# main.net
KiCad netlist of a schematic drawn in Altium Designer
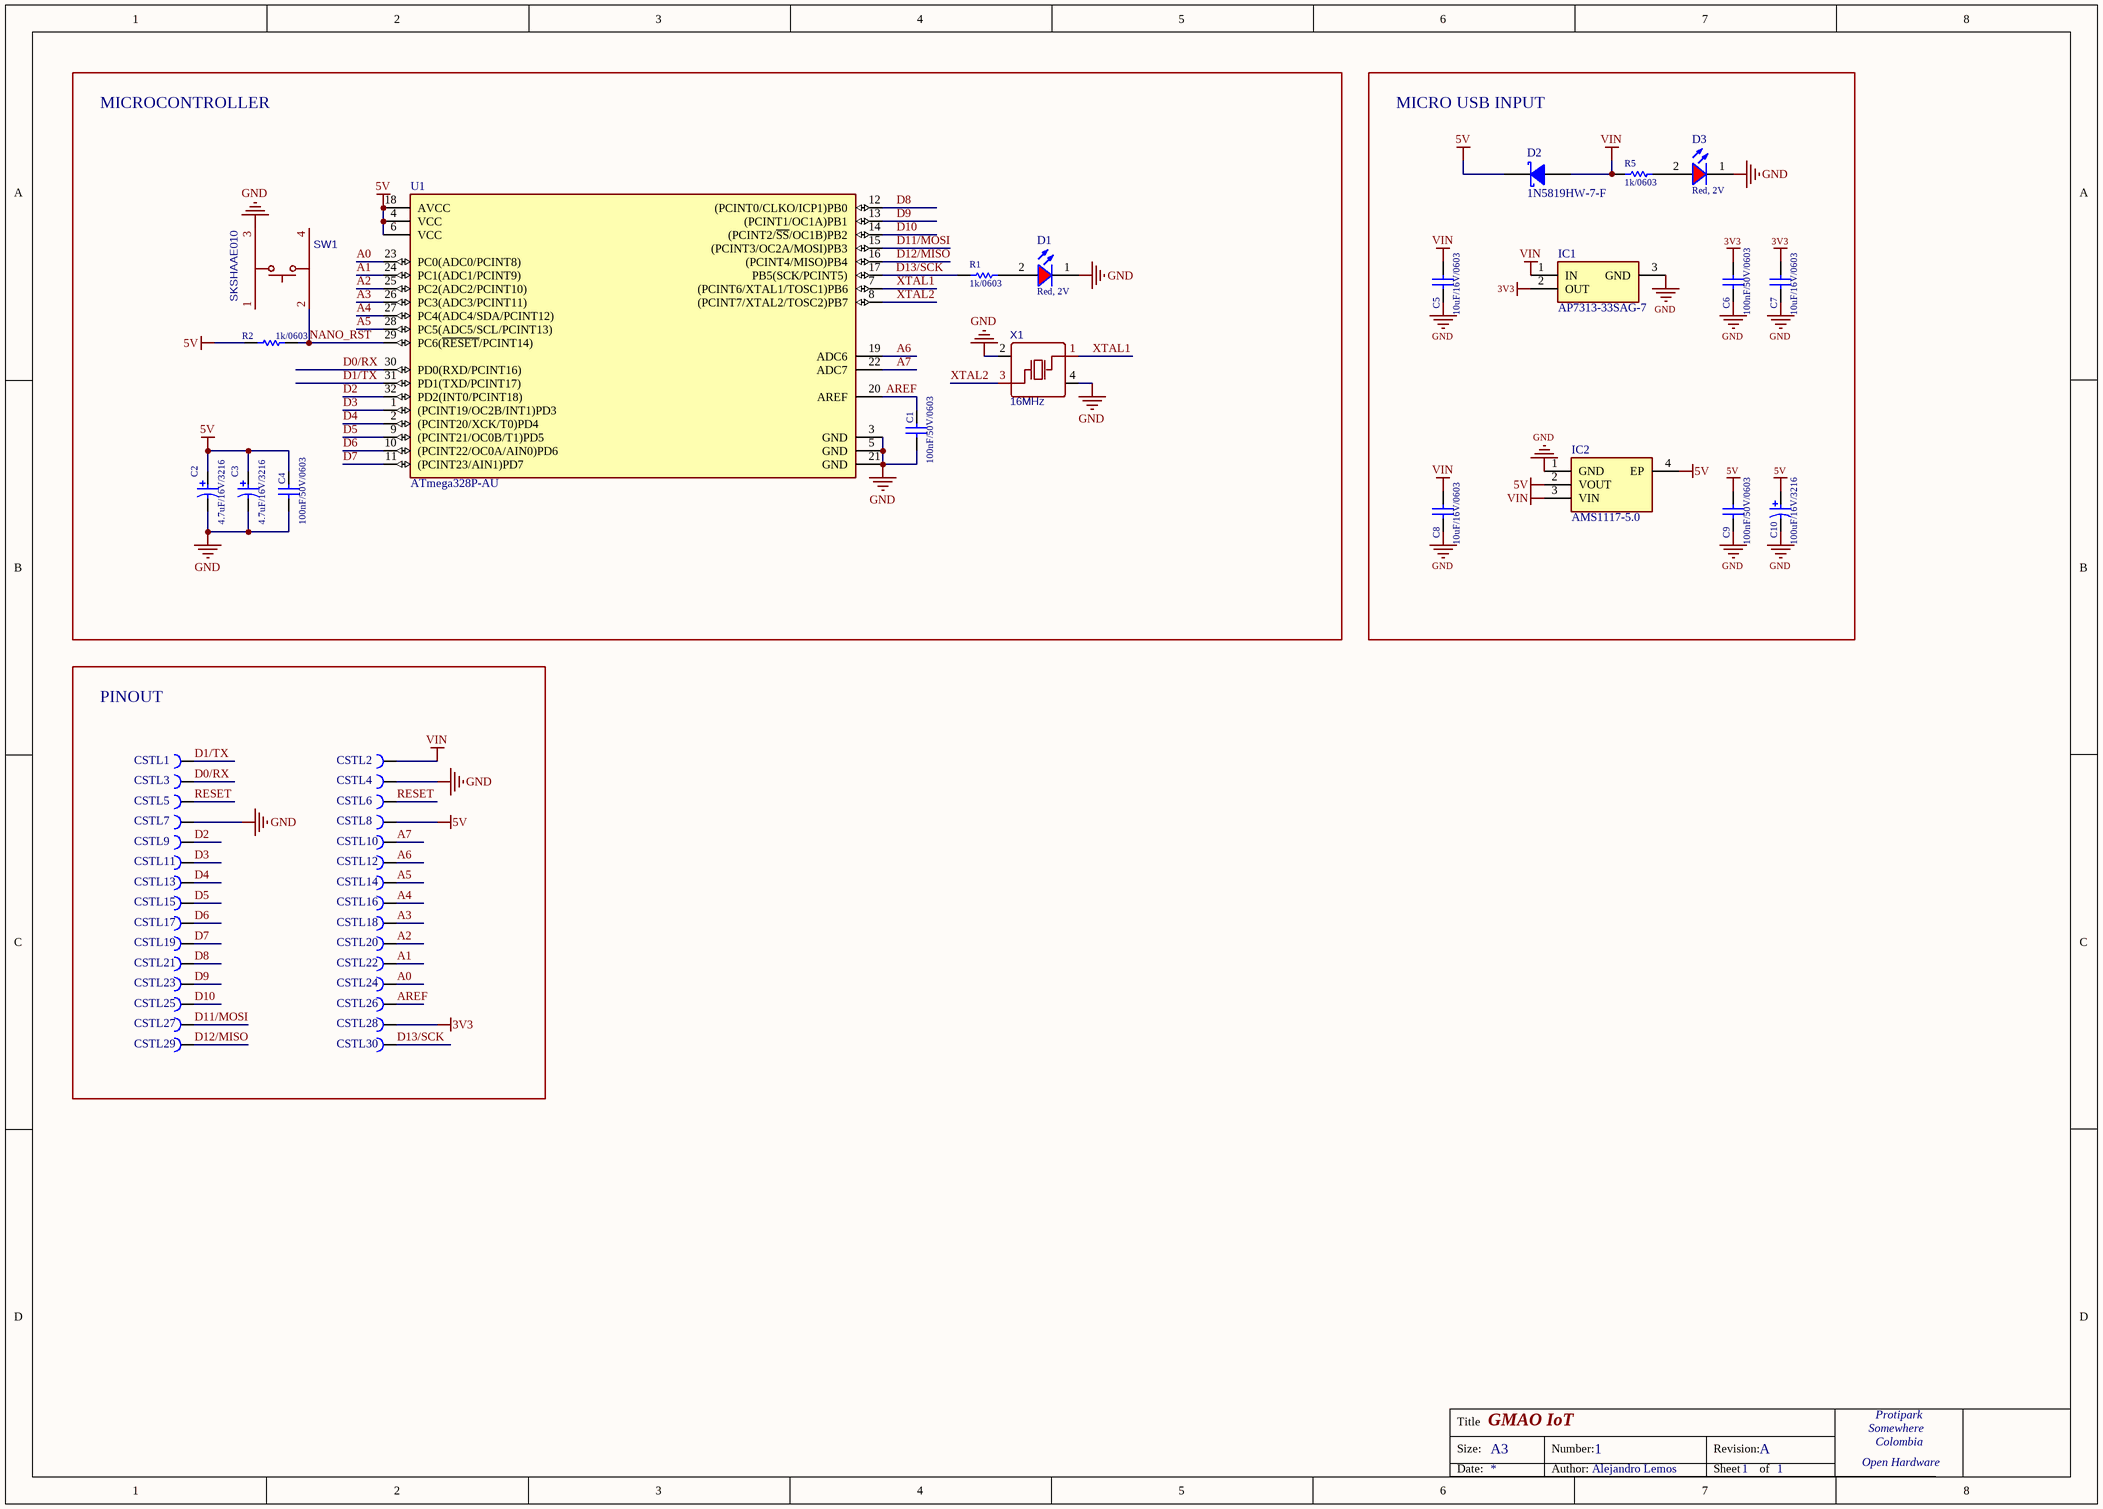
[diagram p0: main.SchDoc]

(export (version "E")
  (design (tool "Eeschema 10.0.6"))
  (components
    (comp (ref "C1")
      (value "100nF/50V/0603")
      (footprint "C0603_L")
      (libsource (lib "seitechs") (part "C_SMD"))
    )
    (comp (ref "C2")
      (value "4.7uF/16V/3216")
      (footprint "KEMT-T491-A_L")
      (description "Tantalum Capacitor, 2.2 uF, +/- 10%, 16 V, -55 to 125 degC, 2-Pin SMD, RoHS, Tape and Reel")
      (fields (field (name "VOLTAGE") "16VDC") (field (name "MANUFACTURER") "Kemet"))
      (libsource (lib "Altium Content Vault") (part "CAP-P-2"))
    )
    (comp (ref "C3")
      (value "4.7uF/16V/3216")
      (footprint "KEMT-T491-A_L")
      (description "Tantalum Capacitor, 2.2 uF, +/- 10%, 16 V, -55 to 125 degC, 2-Pin SMD, RoHS, Tape and Reel")
      (fields (field (name "VOLTAGE") "16VDC") (field (name "MANUFACTURER") "Kemet"))
      (libsource (lib "Altium Content Vault") (part "CAP-P-2"))
    )
    (comp (ref "C4")
      (value "100nF/50V/0603")
      (footprint "C0603_L")
      (libsource (lib "seitechs") (part "C_SMD"))
    )
    (comp (ref "C5")
      (value "10uF/16V/0603")
      (footprint "C0603_L")
      (libsource (lib "seitechs") (part "C_SMD"))
    )
    (comp (ref "C6")
      (value "100nF/50V/0603")
      (footprint "C0603_L")
      (libsource (lib "seitechs") (part "C_SMD"))
    )
    (comp (ref "C7")
      (value "10uF/16V/0603")
      (footprint "C0603_L")
      (libsource (lib "seitechs") (part "C_SMD"))
    )
    (comp (ref "C8")
      (value "10uF/16V/0603")
      (footprint "C0603_L")
      (libsource (lib "seitechs") (part "C_SMD"))
    )
    (comp (ref "C9")
      (value "100nF/50V/0603")
      (footprint "C0603_L")
      (libsource (lib "seitechs") (part "C_SMD"))
    )
    (comp (ref "C10")
      (value "100uF/16V/3216")
      (footprint "KEMT-T491-A_L")
      (description "Tantalum Capacitor, 2.2 uF, +/- 10%, 16 V, -55 to 125 degC, 2-Pin SMD, RoHS, Tape and Reel")
      (fields (field (name "VOLTAGE") "16VDC") (field (name "MANUFACTURER") "Kemet"))
      (libsource (lib "Altium Content Vault") (part "CAP-P-2"))
    )
    (comp (ref "CSTL1")
      (value "CASTELLATED")
      (footprint "CASTELLATED")
      (libsource (lib "seitechs") (part "CASTELLATED"))
    )
    (comp (ref "CSTL2")
      (value "CASTELLATED")
      (footprint "CASTELLATED")
      (libsource (lib "seitechs") (part "CASTELLATED"))
    )
    (comp (ref "CSTL3")
      (value "CASTELLATED")
      (footprint "CASTELLATED")
      (libsource (lib "seitechs") (part "CASTELLATED"))
    )
    (comp (ref "CSTL4")
      (value "CASTELLATED")
      (footprint "CASTELLATED")
      (libsource (lib "seitechs") (part "CASTELLATED"))
    )
    (comp (ref "CSTL5")
      (value "CASTELLATED")
      (footprint "CASTELLATED")
      (libsource (lib "seitechs") (part "CASTELLATED"))
    )
    (comp (ref "CSTL6")
      (value "CASTELLATED")
      (footprint "CASTELLATED")
      (libsource (lib "seitechs") (part "CASTELLATED"))
    )
    (comp (ref "CSTL7")
      (value "CASTELLATED")
      (footprint "CASTELLATED")
      (libsource (lib "seitechs") (part "CASTELLATED"))
    )
    (comp (ref "CSTL8")
      (value "CASTELLATED")
      (footprint "CASTELLATED")
      (libsource (lib "seitechs") (part "CASTELLATED"))
    )
    (comp (ref "CSTL9")
      (value "CASTELLATED")
      (footprint "CASTELLATED")
      (libsource (lib "seitechs") (part "CASTELLATED"))
    )
    (comp (ref "CSTL10")
      (value "CASTELLATED")
      (footprint "CASTELLATED")
      (libsource (lib "seitechs") (part "CASTELLATED"))
    )
    (comp (ref "CSTL11")
      (value "CASTELLATED")
      (footprint "CASTELLATED")
      (libsource (lib "seitechs") (part "CASTELLATED"))
    )
    (comp (ref "CSTL12")
      (value "CASTELLATED")
      (footprint "CASTELLATED")
      (libsource (lib "seitechs") (part "CASTELLATED"))
    )
    (comp (ref "CSTL13")
      (value "CASTELLATED")
      (footprint "CASTELLATED")
      (libsource (lib "seitechs") (part "CASTELLATED"))
    )
    (comp (ref "CSTL14")
      (value "CASTELLATED")
      (footprint "CASTELLATED")
      (libsource (lib "seitechs") (part "CASTELLATED"))
    )
    (comp (ref "CSTL15")
      (value "CASTELLATED")
      (footprint "CASTELLATED")
      (libsource (lib "seitechs") (part "CASTELLATED"))
    )
    (comp (ref "CSTL16")
      (value "CASTELLATED")
      (footprint "CASTELLATED")
      (libsource (lib "seitechs") (part "CASTELLATED"))
    )
    (comp (ref "CSTL17")
      (value "CASTELLATED")
      (footprint "CASTELLATED")
      (libsource (lib "seitechs") (part "CASTELLATED"))
    )
    (comp (ref "CSTL18")
      (value "CASTELLATED")
      (footprint "CASTELLATED")
      (libsource (lib "seitechs") (part "CASTELLATED"))
    )
    (comp (ref "CSTL19")
      (value "CASTELLATED")
      (footprint "CASTELLATED")
      (libsource (lib "seitechs") (part "CASTELLATED"))
    )
    (comp (ref "CSTL20")
      (value "CASTELLATED")
      (footprint "CASTELLATED")
      (libsource (lib "seitechs") (part "CASTELLATED"))
    )
    (comp (ref "CSTL21")
      (value "CASTELLATED")
      (footprint "CASTELLATED")
      (libsource (lib "seitechs") (part "CASTELLATED"))
    )
    (comp (ref "CSTL22")
      (value "CASTELLATED")
      (footprint "CASTELLATED")
      (libsource (lib "seitechs") (part "CASTELLATED"))
    )
    (comp (ref "CSTL23")
      (value "CASTELLATED")
      (footprint "CASTELLATED")
      (libsource (lib "seitechs") (part "CASTELLATED"))
    )
    (comp (ref "CSTL24")
      (value "CASTELLATED")
      (footprint "CASTELLATED")
      (libsource (lib "seitechs") (part "CASTELLATED"))
    )
    (comp (ref "CSTL25")
      (value "CASTELLATED")
      (footprint "CASTELLATED")
      (libsource (lib "seitechs") (part "CASTELLATED"))
    )
    (comp (ref "CSTL26")
      (value "CASTELLATED")
      (footprint "CASTELLATED")
      (libsource (lib "seitechs") (part "CASTELLATED"))
    )
    (comp (ref "CSTL27")
      (value "CASTELLATED")
      (footprint "CASTELLATED")
      (libsource (lib "seitechs") (part "CASTELLATED"))
    )
    (comp (ref "CSTL28")
      (value "CASTELLATED")
      (footprint "CASTELLATED")
      (libsource (lib "seitechs") (part "CASTELLATED"))
    )
    (comp (ref "CSTL29")
      (value "CASTELLATED")
      (footprint "CASTELLATED")
      (libsource (lib "seitechs") (part "CASTELLATED"))
    )
    (comp (ref "CSTL30")
      (value "CASTELLATED")
      (footprint "CASTELLATED")
      (libsource (lib "seitechs") (part "CASTELLATED"))
    )
    (comp (ref "D1")
      (value "Red, 2V")
      (footprint "WL-SMCW_0603_H=0.7mm")
      (description "WL-SMCW SMT Mono-color Chip LED Waterclear, size 0603, Red, 2V, 140deg")
      (fields (field (name "PART NUMBER") "150060RS75000") (field (name "PUBLISHER") "Wurth Elektronik"))
      (libsource (lib "Altium_WL-SMCW (rev20a)") (part "150060RS75000"))
    )
    (comp (ref "D2")
      (value "1N5819HW-7-F")
      (footprint "SOD-123")
      (description "DIODE SCHOTTKY 40V 1A SOD123")
      (fields (field (name "MANUFACTURER") "MCC") (field (name "MANUFACTURER PART NUMBER") "MMSS8050-H-TP"))
      (libsource (lib "seitechs") (part "1N5819HW-7-F"))
    )
    (comp (ref "D3")
      (value "Red, 2V")
      (footprint "WL-SMCW_0603_H=0.7mm")
      (description "WL-SMCW SMT Mono-color Chip LED Waterclear, size 0603, Red, 2V, 140deg")
      (fields (field (name "PART NUMBER") "150060RS75000") (field (name "PUBLISHER") "Wurth Elektronik"))
      (libsource (lib "Altium_WL-SMCW (rev20a)") (part "150060RS75000"))
    )
    (comp (ref "IC1")
      (value "AP7313-33SAG-7")
      (footprint "SamacSys:SOT96P240X110-3N")
      (description "Integrated Circuit")
      (fields (field (name "MOUSER PART NUMBER") "621-AP7313-33SAG-7"))
      (libsource (lib "*") (part "AP7313-33SAG-7"))
    )
    (comp (ref "IC2")
      (value "AMS1117-5.0")
      (footprint "SamacSys:SOT290P700X180-4N")
      (description "Integrated Circuit")
      (libsource (lib "*") (part "AMS1117-5.0"))
    )
    (comp (ref "R1") (value "1k/0603") (footprint "R0603_N") (libsource (lib "seitechs") (part "R_SMD")))
    (comp (ref "R2") (value "1k/0603") (footprint "R0603_N") (libsource (lib "seitechs") (part "R_SMD")))
    (comp (ref "R5") (value "1k/0603") (footprint "R0603_N") (libsource (lib "seitechs") (part "R_SMD")))
    (comp (ref "SW1")
      (value "SKSHAAE010")
      (footprint "SW-SMD_4P-L3.2-W2.9-P2.20-LS3.4")
      (description "SWITCH")
      (fields (field (name "BOM_SUPPLIER PART") "C262415") (field (name "CONTRIBUTOR") "LCSC"))
      (libsource (lib "seitechs") (part "SKSHAAE010"))
    )
    (comp (ref "U1")
      (value "ATmega328P-AU")
      (footprint "FP-32A-MFG")
      (description "IC MCU 8BIT 32KB FLASH 32TQFP")
      (fields
        (field (name "MANUFACTURER") "Microchip")
        (field (name "OCTOPART") "https://octopart.com/atmega328p-au-microchip-77760215")
      )
      (libsource (lib "Altium Content Vault") (part "f5fbdcb2c0c597ef7d3dd1575aef21a"))
    )
    (comp (ref "X1")
      (value "16MHz")
      (footprint "CRYSTAL-SMD_4P-L3.2-W2.5-BL")
      (fields
        (field (name "BOM_MANUFACTURER PART") "X322516MOB4SI")
        (field (name "BOM_SUPPLIER PART") "C12668")
      )
      (libsource (lib "seitechs") (part "16MHz"))
    )
  )
  (nets
    (net (code "1") (name "/A0") (class "Default")
      (node (ref "CSTL24") (pin "0") (pinfunction "0_0") (pintype "passive"))
      (node (ref "U1") (pin "23") (pinfunction "PC0(ADC0/PCINT8)_23") (pintype "bidirectional"))
    )
    (net (code "2") (name "/A1") (class "Default")
      (node (ref "CSTL22") (pin "0") (pinfunction "0_0") (pintype "passive"))
      (node (ref "U1") (pin "24") (pinfunction "PC1(ADC1/PCINT9)_24") (pintype "bidirectional"))
    )
    (net (code "3") (name "/A2") (class "Default")
      (node (ref "CSTL20") (pin "0") (pinfunction "0_0") (pintype "passive"))
      (node (ref "U1") (pin "25") (pinfunction "PC2(ADC2/PCINT10)_25") (pintype "bidirectional"))
    )
    (net (code "4") (name "/A3") (class "Default")
      (node (ref "CSTL18") (pin "0") (pinfunction "0_0") (pintype "passive"))
      (node (ref "U1") (pin "26") (pinfunction "PC3(ADC3/PCINT11)_26") (pintype "bidirectional"))
    )
    (net (code "5") (name "/A4") (class "Default")
      (node (ref "CSTL16") (pin "0") (pinfunction "0_0") (pintype "passive"))
      (node (ref "U1") (pin "27") (pinfunction "PC4(ADC4/SDA/PCINT12)_27") (pintype "bidirectional"))
    )
    (net (code "6") (name "/A5") (class "Default")
      (node (ref "CSTL14") (pin "0") (pinfunction "0_0") (pintype "passive"))
      (node (ref "U1") (pin "28") (pinfunction "PC5(ADC5/SCL/PCINT13)_28") (pintype "bidirectional"))
    )
    (net (code "7") (name "/A6") (class "Default")
      (node (ref "CSTL12") (pin "0") (pinfunction "0_0") (pintype "passive"))
      (node (ref "U1") (pin "19") (pinfunction "ADC6_19") (pintype "power_in"))
    )
    (net (code "8") (name "/A7") (class "Default")
      (node (ref "CSTL10") (pin "0") (pinfunction "0_0") (pintype "passive"))
      (node (ref "U1") (pin "22") (pinfunction "ADC7_22") (pintype "passive"))
    )
    (net (code "9") (name "/AREF") (class "Default")
      (node (ref "C1") (pin "1") (pinfunction "1_1") (pintype "passive"))
      (node (ref "CSTL26") (pin "0") (pinfunction "0_0") (pintype "passive"))
      (node (ref "U1") (pin "20") (pinfunction "AREF_20") (pintype "passive"))
    )
    (net (code "10") (name "/D0{slash}RX") (class "Default")
      (node (ref "CSTL3") (pin "0") (pinfunction "0_0") (pintype "passive"))
      (node (ref "U1") (pin "30") (pinfunction "PD0(RXD/PCINT16)_30") (pintype "bidirectional"))
    )
    (net (code "11") (name "/D1{slash}TX") (class "Default")
      (node (ref "CSTL1") (pin "0") (pinfunction "0_0") (pintype "passive"))
      (node (ref "U1") (pin "31") (pinfunction "PD1(TXD/PCINT17)_31") (pintype "bidirectional"))
    )
    (net (code "12") (name "/D2") (class "Default")
      (node (ref "CSTL9") (pin "0") (pinfunction "0_0") (pintype "passive"))
      (node (ref "U1") (pin "32") (pinfunction "PD2(INT0/PCINT18)_32") (pintype "bidirectional"))
    )
    (net (code "13") (name "/D3") (class "Default")
      (node (ref "CSTL11") (pin "0") (pinfunction "0_0") (pintype "passive"))
      (node (ref "U1") (pin "1") (pinfunction "(PCINT19/OC2B/INT1)PD3_1") (pintype "bidirectional"))
    )
    (net (code "14") (name "/D4") (class "Default")
      (node (ref "CSTL13") (pin "0") (pinfunction "0_0") (pintype "passive"))
      (node (ref "U1") (pin "2") (pinfunction "(PCINT20/XCK/T0)PD4_2") (pintype "bidirectional"))
    )
    (net (code "15") (name "/D5") (class "Default")
      (node (ref "CSTL15") (pin "0") (pinfunction "0_0") (pintype "passive"))
      (node (ref "U1") (pin "9") (pinfunction "(PCINT21/OC0B/T1)PD5_9") (pintype "bidirectional"))
    )
    (net (code "16") (name "/D6") (class "Default")
      (node (ref "CSTL17") (pin "0") (pinfunction "0_0") (pintype "passive"))
      (node (ref "U1") (pin "10") (pinfunction "(PCINT22/OC0A/AIN0)PD6_10") (pintype "bidirectional"))
    )
    (net (code "17") (name "/D7") (class "Default")
      (node (ref "CSTL19") (pin "0") (pinfunction "0_0") (pintype "passive"))
      (node (ref "U1") (pin "11") (pinfunction "(PCINT23/AIN1)PD7_11") (pintype "bidirectional"))
    )
    (net (code "18") (name "/D8") (class "Default")
      (node (ref "CSTL21") (pin "0") (pinfunction "0_0") (pintype "passive"))
      (node (ref "U1") (pin "12") (pinfunction "(PCINT0/CLKO/ICP1)PB0_12") (pintype "bidirectional"))
    )
    (net (code "19") (name "/D9") (class "Default")
      (node (ref "CSTL23") (pin "0") (pinfunction "0_0") (pintype "passive"))
      (node (ref "U1") (pin "13") (pinfunction "(PCINT1/OC1A)PB1_13") (pintype "bidirectional"))
    )
    (net (code "20") (name "/D10") (class "Default")
      (node (ref "CSTL25") (pin "0") (pinfunction "0_0") (pintype "passive"))
      (node (ref "U1") (pin "14") (pinfunction "(PCINT2/~{SS}/OC1B)PB2_14") (pintype "bidirectional"))
    )
    (net (code "21") (name "/D11{slash}MOSI") (class "Default")
      (node (ref "CSTL27") (pin "0") (pinfunction "0_0") (pintype "passive"))
      (node (ref "U1") (pin "15") (pinfunction "(PCINT3/OC2A/MOSI)PB3_15") (pintype "bidirectional"))
    )
    (net (code "22") (name "/D12{slash}MISO") (class "Default")
      (node (ref "CSTL29") (pin "0") (pinfunction "0_0") (pintype "passive"))
      (node (ref "U1") (pin "16") (pinfunction "(PCINT4/MISO)PB4_16") (pintype "bidirectional"))
    )
    (net (code "23") (name "/D13{slash}SCK") (class "Default")
      (node (ref "CSTL30") (pin "0") (pinfunction "0_0") (pintype "passive"))
      (node (ref "R1") (pin "2") (pinfunction "2_2") (pintype "passive"))
      (node (ref "U1") (pin "17") (pinfunction "PB5(SCK/PCINT5)_17") (pintype "bidirectional"))
    )
    (net (code "24") (name "/NANO_RST") (class "Default")
      (node (ref "R2") (pin "2") (pinfunction "2_2") (pintype "passive"))
      (node (ref "SW1") (pin "2") (pinfunction "2_2") (pintype "passive"))
      (node (ref "U1") (pin "29") (pinfunction "PC6(~{RESET}/PCINT14)_29") (pintype "bidirectional"))
    )
    (net (code "25") (name "/RESET") (class "Default")
      (node (ref "CSTL5") (pin "0") (pinfunction "0_0") (pintype "passive"))
      (node (ref "CSTL6") (pin "0") (pinfunction "0_0") (pintype "passive"))
    )
    (net (code "26") (name "/XTAL1") (class "Default")
      (node (ref "U1") (pin "7") (pinfunction "(PCINT6/XTAL1/TOSC1)PB6_7") (pintype "bidirectional"))
      (node (ref "X1") (pin "1") (pinfunction "OSC1_1") (pintype "passive"))
    )
    (net (code "27") (name "/XTAL2") (class "Default")
      (node (ref "U1") (pin "8") (pinfunction "(PCINT7/XTAL2/TOSC2)PB7_8") (pintype "bidirectional"))
      (node (ref "X1") (pin "3") (pinfunction "OSC2_3") (pintype "passive"))
    )
    (net (code "28") (name "3V3") (class "Default")
      (node (ref "C6") (pin "2") (pinfunction "2_2") (pintype "passive"))
      (node (ref "C7") (pin "2") (pinfunction "2_2") (pintype "passive"))
      (node (ref "CSTL28") (pin "0") (pinfunction "0_0") (pintype "passive"))
      (node (ref "IC1") (pin "2") (pinfunction "OUT_2") (pintype "passive"))
    )
    (net (code "29") (name "5V") (class "Default")
      (node (ref "C10") (pin "1") (pinfunction "1_1") (pintype "passive"))
      (node (ref "C2") (pin "1") (pinfunction "1_1") (pintype "passive"))
      (node (ref "C3") (pin "1") (pinfunction "1_1") (pintype "passive"))
      (node (ref "C4") (pin "2") (pinfunction "2_2") (pintype "passive"))
      (node (ref "C9") (pin "2") (pinfunction "2_2") (pintype "passive"))
      (node (ref "CSTL8") (pin "0") (pinfunction "0_0") (pintype "passive"))
      (node (ref "D2") (pin "2") (pinfunction "K_2") (pintype "passive"))
      (node (ref "IC2") (pin "2") (pinfunction "VOUT_2") (pintype "passive"))
      (node (ref "IC2") (pin "4") (pinfunction "EP_4") (pintype "passive"))
      (node (ref "R2") (pin "1") (pinfunction "1_1") (pintype "passive"))
      (node (ref "U1") (pin "18") (pinfunction "AVCC_18") (pintype "power_in"))
      (node (ref "U1") (pin "4") (pinfunction "VCC_4") (pintype "power_in"))
      (node (ref "U1") (pin "6") (pinfunction "VCC_6") (pintype "power_in"))
    )
    (net (code "30") (name "GND") (class "Default")
      (node (ref "C1") (pin "2") (pinfunction "2_2") (pintype "passive"))
      (node (ref "C10") (pin "2") (pinfunction "2_2") (pintype "passive"))
      (node (ref "C2") (pin "2") (pinfunction "2_2") (pintype "passive"))
      (node (ref "C3") (pin "2") (pinfunction "2_2") (pintype "passive"))
      (node (ref "C4") (pin "1") (pinfunction "1_1") (pintype "passive"))
      (node (ref "C5") (pin "1") (pinfunction "1_1") (pintype "passive"))
      (node (ref "C6") (pin "1") (pinfunction "1_1") (pintype "passive"))
      (node (ref "C7") (pin "1") (pinfunction "1_1") (pintype "passive"))
      (node (ref "C8") (pin "1") (pinfunction "1_1") (pintype "passive"))
      (node (ref "C9") (pin "1") (pinfunction "1_1") (pintype "passive"))
      (node (ref "CSTL4") (pin "0") (pinfunction "0_0") (pintype "passive"))
      (node (ref "CSTL7") (pin "0") (pinfunction "0_0") (pintype "passive"))
      (node (ref "D1") (pin "1") (pinfunction "K_1") (pintype "passive"))
      (node (ref "D3") (pin "1") (pinfunction "K_1") (pintype "passive"))
      (node (ref "IC1") (pin "3") (pinfunction "GND_3") (pintype "power_in"))
      (node (ref "IC2") (pin "1") (pinfunction "GND_1") (pintype "passive"))
      (node (ref "SW1") (pin "3") (pinfunction "3_3") (pintype "passive"))
      (node (ref "U1") (pin "21") (pinfunction "GND_21") (pintype "power_in"))
      (node (ref "U1") (pin "3") (pinfunction "GND_3") (pintype "power_in"))
      (node (ref "U1") (pin "5") (pinfunction "GND_5") (pintype "power_in"))
      (node (ref "X1") (pin "2") (pinfunction "GND_2") (pintype "passive"))
      (node (ref "X1") (pin "4") (pinfunction "GND_4") (pintype "passive"))
    )
    (net (code "31") (name "Net-(D1-A)") (class "Default")
      (node (ref "D1") (pin "2") (pinfunction "A_2") (pintype "passive"))
      (node (ref "R1") (pin "1") (pinfunction "1_1") (pintype "passive"))
    )
    (net (code "32") (name "Net-(D3-A)") (class "Default")
      (node (ref "D3") (pin "2") (pinfunction "A_2") (pintype "passive"))
      (node (ref "R5") (pin "1") (pinfunction "1_1") (pintype "passive"))
    )
    (net (code "33") (name "VIN") (class "Default")
      (node (ref "C5") (pin "2") (pinfunction "2_2") (pintype "passive"))
      (node (ref "C8") (pin "2") (pinfunction "2_2") (pintype "passive"))
      (node (ref "CSTL2") (pin "0") (pinfunction "0_0") (pintype "passive"))
      (node (ref "D2") (pin "1") (pinfunction "A_1") (pintype "passive"))
      (node (ref "IC1") (pin "1") (pinfunction "IN_1") (pintype "passive"))
      (node (ref "IC2") (pin "3") (pinfunction "VIN_3") (pintype "passive"))
      (node (ref "R5") (pin "2") (pinfunction "2_2") (pintype "passive"))
    )
    (net (code "34") (name "unconnected-(SW1-Pad1)") (class "Default")
      (node (ref "SW1") (pin "1") (pinfunction "1_1") (pintype "passive"))
    )
    (net (code "35") (name "unconnected-(SW1-Pad4)") (class "Default")
      (node (ref "SW1") (pin "4") (pinfunction "4_4") (pintype "passive"))
    )
  )
)
